# PCBschematic.net
KiCad netlist of a schematic drawn in EAGLE
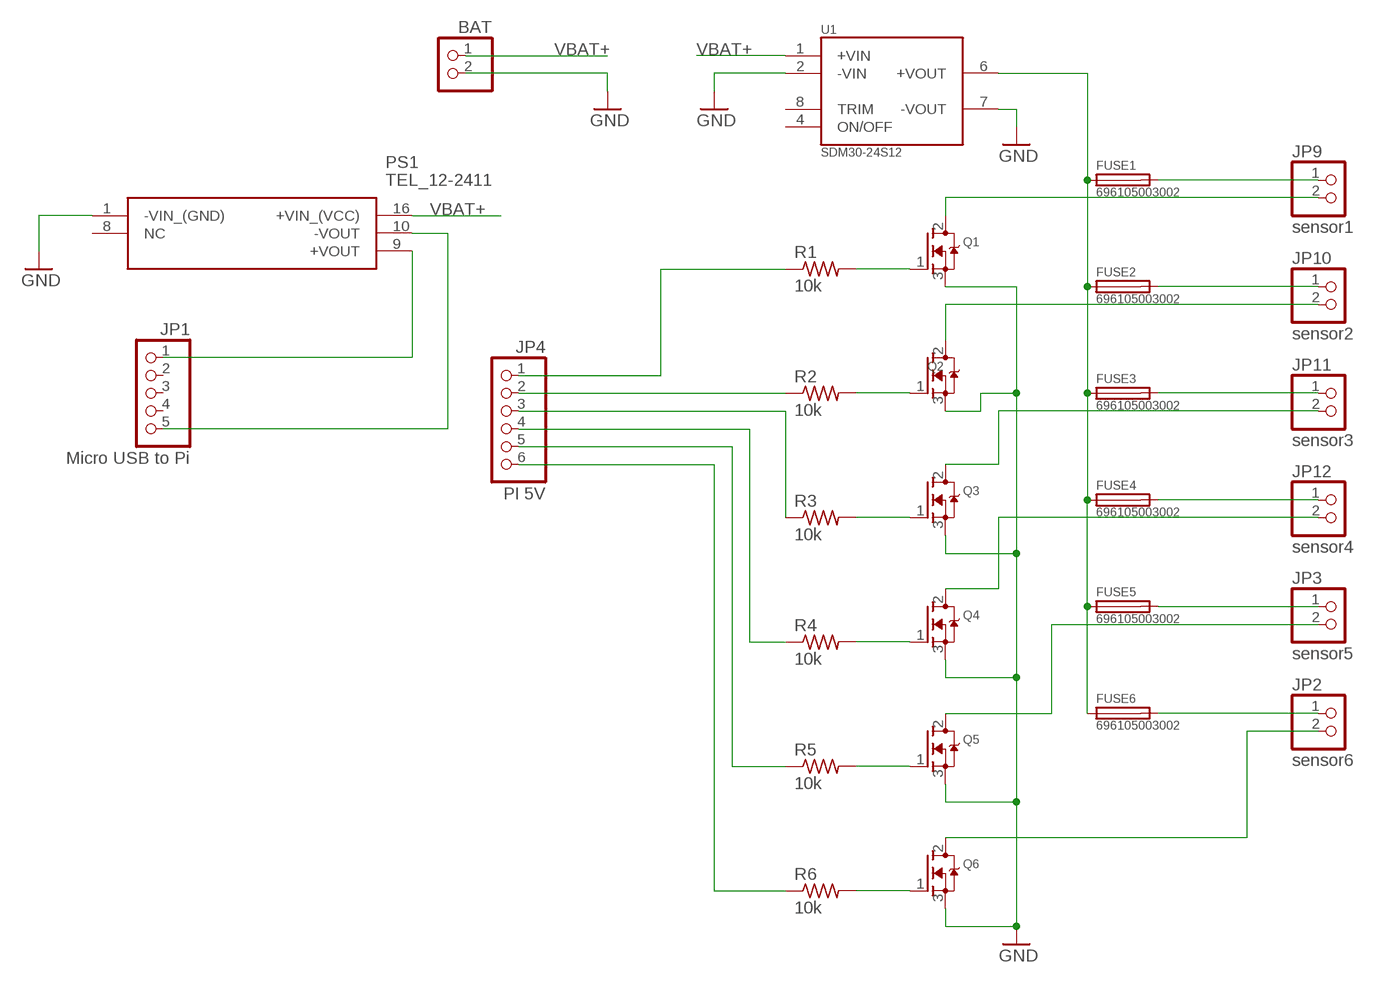
[diagram p0: schematic, sheet 1]

(export (version "E")
  (design (tool "Eeschema 10.0.6"))
  (components
    (comp (ref "BAT")
      (value "PINHD-1X2")
      (footprint "eagle-import:1X02")
      (libsource (lib "eagle-import") (part "PINHD-1X2"))
    )
    (comp (ref "FUSE1")
      (value "696105003002")
      (footprint "eagle-import:FUSE_696105003002")
      (fields (field (name "MF") "Wurth Electronics"))
      (libsource (lib "eagle-import") (part "696105003002"))
    )
    (comp (ref "FUSE2")
      (value "696105003002")
      (footprint "eagle-import:FUSE_696105003002")
      (fields (field (name "MF") "Wurth Electronics"))
      (libsource (lib "eagle-import") (part "696105003002"))
    )
    (comp (ref "FUSE3")
      (value "696105003002")
      (footprint "eagle-import:FUSE_696105003002")
      (fields (field (name "MF") "Wurth Electronics"))
      (libsource (lib "eagle-import") (part "696105003002"))
    )
    (comp (ref "FUSE4")
      (value "696105003002")
      (footprint "eagle-import:FUSE_696105003002")
      (fields (field (name "MF") "Wurth Electronics"))
      (libsource (lib "eagle-import") (part "696105003002"))
    )
    (comp (ref "FUSE5")
      (value "696105003002")
      (footprint "eagle-import:FUSE_696105003002")
      (fields (field (name "MF") "Wurth Electronics"))
      (libsource (lib "eagle-import") (part "696105003002"))
    )
    (comp (ref "FUSE6")
      (value "696105003002")
      (footprint "eagle-import:FUSE_696105003002")
      (fields (field (name "MF") "Wurth Electronics"))
      (libsource (lib "eagle-import") (part "696105003002"))
    )
    (comp (ref "JP1")
      (value "Micro USB to Pi")
      (footprint "eagle-import:1X05")
      (libsource (lib "eagle-import") (part "PINHD-1X5"))
    )
    (comp (ref "JP2")
      (value "sensor6")
      (footprint "eagle-import:1X02")
      (libsource (lib "eagle-import") (part "PINHD-1X2"))
    )
    (comp (ref "JP3")
      (value "sensor5")
      (footprint "eagle-import:1X02")
      (libsource (lib "eagle-import") (part "PINHD-1X2"))
    )
    (comp (ref "JP4")
      (value "PI 5V")
      (footprint "eagle-import:1X06")
      (libsource (lib "eagle-import") (part "PINHD-1X6"))
    )
    (comp (ref "JP9")
      (value "sensor1")
      (footprint "eagle-import:1X02")
      (libsource (lib "eagle-import") (part "PINHD-1X2"))
    )
    (comp (ref "JP10")
      (value "sensor2")
      (footprint "eagle-import:1X02")
      (libsource (lib "eagle-import") (part "PINHD-1X2"))
    )
    (comp (ref "JP11")
      (value "sensor3")
      (footprint "eagle-import:1X02")
      (libsource (lib "eagle-import") (part "PINHD-1X2"))
    )
    (comp (ref "JP12")
      (value "sensor4")
      (footprint "eagle-import:1X02")
      (libsource (lib "eagle-import") (part "PINHD-1X2"))
    )
    (comp (ref "PS1")
      (value "TEL_12-2411")
      (footprint "eagle-import:TEL122411")
      (fields
        (field (name "MANUFACTURER_PART_NUMBER") "TEL 12-2411")
        (field (name "MOUSER_PART_NUMBER") "495-TEL12-2411")
      )
      (libsource (lib "eagle-import") (part "TEL_12-2411"))
    )
    (comp (ref "Q1")
      (value "MOSFET-NGDS_TO220V")
      (footprint "eagle-import:TO220V")
      (libsource (lib "eagle-import") (part "MOSFET-NGDS_TO220V"))
    )
    (comp (ref "Q2")
      (value "MOSFET-NGDS_TO220V")
      (footprint "eagle-import:TO220V")
      (libsource (lib "eagle-import") (part "MOSFET-NGDS_TO220V"))
    )
    (comp (ref "Q3")
      (value "MOSFET-NGDS_TO220V")
      (footprint "eagle-import:TO220V")
      (libsource (lib "eagle-import") (part "MOSFET-NGDS_TO220V"))
    )
    (comp (ref "Q4")
      (value "MOSFET-NGDS_TO220V")
      (footprint "eagle-import:TO220V")
      (libsource (lib "eagle-import") (part "MOSFET-NGDS_TO220V"))
    )
    (comp (ref "Q5")
      (value "MOSFET-NGDS_TO220V")
      (footprint "eagle-import:TO220V")
      (libsource (lib "eagle-import") (part "MOSFET-NGDS_TO220V"))
    )
    (comp (ref "Q6")
      (value "MOSFET-NGDS_TO220V")
      (footprint "eagle-import:TO220V")
      (libsource (lib "eagle-import") (part "MOSFET-NGDS_TO220V"))
    )
    (comp (ref "R1")
      (value "10k")
      (footprint "eagle-import:M0805")
      (libsource (lib "eagle-import") (part "R-US_M0805"))
    )
    (comp (ref "R2")
      (value "10k")
      (footprint "eagle-import:M0805")
      (libsource (lib "eagle-import") (part "R-US_M0805"))
    )
    (comp (ref "R3")
      (value "10k")
      (footprint "eagle-import:M0805")
      (libsource (lib "eagle-import") (part "R-US_M0805"))
    )
    (comp (ref "R4")
      (value "10k")
      (footprint "eagle-import:M0805")
      (libsource (lib "eagle-import") (part "R-US_M0805"))
    )
    (comp (ref "R5")
      (value "10k")
      (footprint "eagle-import:M0805")
      (libsource (lib "eagle-import") (part "R-US_M0805"))
    )
    (comp (ref "R6")
      (value "10k")
      (footprint "eagle-import:M0805")
      (libsource (lib "eagle-import") (part "R-US_M0805"))
    )
    (comp (ref "U1")
      (value "SDM30-24S12")
      (footprint "eagle-import:CONV_SDM30-24S12")
      (fields (field (name "DIGI-KEY_PART_NUMBER") "1866-4449-ND") (field (name "MF") "MEAN WELL"))
      (libsource (lib "eagle-import") (part "SDM30-24S12"))
    )
  )
  (nets
    (net (code "1") (name "/VBAT+") (class "Default")
      (node (ref "BAT") (pin "1") (pinfunction "1_1") (pintype "passive"))
      (node (ref "PS1") (pin "16") (pinfunction "+VIN_(VCC)_16") (pintype "bidirectional"))
      (node (ref "U1") (pin "1") (pinfunction "+VIN_1") (pintype "input"))
    )
    (net (code "2") (name "GND") (class "Default")
      (node (ref "BAT") (pin "2") (pinfunction "2_2") (pintype "passive"))
      (node (ref "PS1") (pin "1") (pinfunction "-VIN_(GND)_1") (pintype "bidirectional"))
      (node (ref "Q1") (pin "3") (pinfunction "S_3") (pintype "bidirectional"))
      (node (ref "Q2") (pin "3") (pinfunction "S_3") (pintype "bidirectional"))
      (node (ref "Q3") (pin "3") (pinfunction "S_3") (pintype "bidirectional"))
      (node (ref "Q4") (pin "3") (pinfunction "S_3") (pintype "bidirectional"))
      (node (ref "Q5") (pin "3") (pinfunction "S_3") (pintype "bidirectional"))
      (node (ref "Q6") (pin "3") (pinfunction "S_3") (pintype "bidirectional"))
      (node (ref "U1") (pin "2") (pinfunction "-VIN_2") (pintype "input"))
      (node (ref "U1") (pin "7") (pinfunction "-VOUT_7") (pintype "output"))
    )
    (net (code "3") (name "Net-(FUSE1-Pad2)") (class "Default")
      (node (ref "FUSE1") (pin "2") (pinfunction "2_2") (pintype "passive"))
      (node (ref "JP9") (pin "1") (pinfunction "1_1") (pintype "passive"))
    )
    (net (code "4") (name "Net-(FUSE2-Pad2)") (class "Default")
      (node (ref "FUSE2") (pin "2") (pinfunction "2_2") (pintype "passive"))
      (node (ref "JP10") (pin "1") (pinfunction "1_1") (pintype "passive"))
    )
    (net (code "5") (name "Net-(FUSE3-Pad2)") (class "Default")
      (node (ref "FUSE3") (pin "2") (pinfunction "2_2") (pintype "passive"))
      (node (ref "JP11") (pin "1") (pinfunction "1_1") (pintype "passive"))
    )
    (net (code "6") (name "Net-(FUSE4-Pad2)") (class "Default")
      (node (ref "FUSE4") (pin "2") (pinfunction "2_2") (pintype "passive"))
      (node (ref "JP12") (pin "1") (pinfunction "1_1") (pintype "passive"))
    )
    (net (code "7") (name "Net-(FUSE5-Pad2)") (class "Default")
      (node (ref "FUSE5") (pin "2") (pinfunction "2_2") (pintype "passive"))
      (node (ref "JP3") (pin "1") (pinfunction "1_1") (pintype "passive"))
    )
    (net (code "8") (name "Net-(FUSE6-Pad2)") (class "Default")
      (node (ref "FUSE6") (pin "2") (pinfunction "2_2") (pintype "passive"))
      (node (ref "JP2") (pin "1") (pinfunction "1_1") (pintype "passive"))
    )
    (net (code "9") (name "Net-(JP4-Pad1)") (class "Default")
      (node (ref "JP4") (pin "1") (pinfunction "1_1") (pintype "passive"))
      (node (ref "R1") (pin "1") (pinfunction "1_1") (pintype "passive"))
    )
    (net (code "10") (name "Net-(JP4-Pad2)") (class "Default")
      (node (ref "JP4") (pin "2") (pinfunction "2_2") (pintype "passive"))
      (node (ref "R2") (pin "1") (pinfunction "1_1") (pintype "passive"))
    )
    (net (code "11") (name "Net-(JP4-Pad3)") (class "Default")
      (node (ref "JP4") (pin "3") (pinfunction "3_3") (pintype "passive"))
      (node (ref "R3") (pin "1") (pinfunction "1_1") (pintype "passive"))
    )
    (net (code "12") (name "Net-(JP4-Pad4)") (class "Default")
      (node (ref "JP4") (pin "4") (pinfunction "4_4") (pintype "passive"))
      (node (ref "R4") (pin "1") (pinfunction "1_1") (pintype "passive"))
    )
    (net (code "13") (name "Net-(JP4-Pad5)") (class "Default")
      (node (ref "JP4") (pin "5") (pinfunction "5_5") (pintype "passive"))
      (node (ref "R5") (pin "1") (pinfunction "1_1") (pintype "passive"))
    )
    (net (code "14") (name "Net-(JP4-Pad6)") (class "Default")
      (node (ref "JP4") (pin "6") (pinfunction "6_6") (pintype "passive"))
      (node (ref "R6") (pin "1") (pinfunction "1_1") (pintype "passive"))
    )
    (net (code "15") (name "Net-(PS1-+VOUT)") (class "Default")
      (node (ref "JP1") (pin "1") (pinfunction "1_1") (pintype "passive"))
      (node (ref "PS1") (pin "9") (pinfunction "+VOUT_9") (pintype "bidirectional"))
    )
    (net (code "16") (name "Net-(PS1--VOUT)") (class "Default")
      (node (ref "JP1") (pin "5") (pinfunction "5_5") (pintype "passive"))
      (node (ref "PS1") (pin "10") (pinfunction "-VOUT_10") (pintype "bidirectional"))
    )
    (net (code "17") (name "Net-(Q1-D)") (class "Default")
      (node (ref "JP9") (pin "2") (pinfunction "2_2") (pintype "passive"))
      (node (ref "Q1") (pin "2") (pinfunction "D_2") (pintype "bidirectional"))
    )
    (net (code "18") (name "Net-(Q1-G)") (class "Default")
      (node (ref "Q1") (pin "1") (pinfunction "G_1") (pintype "bidirectional"))
      (node (ref "R1") (pin "2") (pinfunction "2_2") (pintype "passive"))
    )
    (net (code "19") (name "Net-(Q2-D)") (class "Default")
      (node (ref "JP10") (pin "2") (pinfunction "2_2") (pintype "passive"))
      (node (ref "Q2") (pin "2") (pinfunction "D_2") (pintype "bidirectional"))
    )
    (net (code "20") (name "Net-(Q2-G)") (class "Default")
      (node (ref "Q2") (pin "1") (pinfunction "G_1") (pintype "bidirectional"))
      (node (ref "R2") (pin "2") (pinfunction "2_2") (pintype "passive"))
    )
    (net (code "21") (name "Net-(Q3-D)") (class "Default")
      (node (ref "JP11") (pin "2") (pinfunction "2_2") (pintype "passive"))
      (node (ref "Q3") (pin "2") (pinfunction "D_2") (pintype "bidirectional"))
    )
    (net (code "22") (name "Net-(Q3-G)") (class "Default")
      (node (ref "Q3") (pin "1") (pinfunction "G_1") (pintype "bidirectional"))
      (node (ref "R3") (pin "2") (pinfunction "2_2") (pintype "passive"))
    )
    (net (code "23") (name "Net-(Q4-D)") (class "Default")
      (node (ref "JP12") (pin "2") (pinfunction "2_2") (pintype "passive"))
      (node (ref "Q4") (pin "2") (pinfunction "D_2") (pintype "bidirectional"))
    )
    (net (code "24") (name "Net-(Q4-G)") (class "Default")
      (node (ref "Q4") (pin "1") (pinfunction "G_1") (pintype "bidirectional"))
      (node (ref "R4") (pin "2") (pinfunction "2_2") (pintype "passive"))
    )
    (net (code "25") (name "Net-(Q5-D)") (class "Default")
      (node (ref "JP3") (pin "2") (pinfunction "2_2") (pintype "passive"))
      (node (ref "Q5") (pin "2") (pinfunction "D_2") (pintype "bidirectional"))
    )
    (net (code "26") (name "Net-(Q5-G)") (class "Default")
      (node (ref "Q5") (pin "1") (pinfunction "G_1") (pintype "bidirectional"))
      (node (ref "R5") (pin "2") (pinfunction "2_2") (pintype "passive"))
    )
    (net (code "27") (name "Net-(Q6-D)") (class "Default")
      (node (ref "JP2") (pin "2") (pinfunction "2_2") (pintype "passive"))
      (node (ref "Q6") (pin "2") (pinfunction "D_2") (pintype "bidirectional"))
    )
    (net (code "28") (name "Net-(Q6-G)") (class "Default")
      (node (ref "Q6") (pin "1") (pinfunction "G_1") (pintype "bidirectional"))
      (node (ref "R6") (pin "2") (pinfunction "2_2") (pintype "passive"))
    )
    (net (code "29") (name "Net-(U1-+VOUT)") (class "Default")
      (node (ref "FUSE1") (pin "1") (pinfunction "1_1") (pintype "passive"))
      (node (ref "FUSE2") (pin "1") (pinfunction "1_1") (pintype "passive"))
      (node (ref "FUSE3") (pin "1") (pinfunction "1_1") (pintype "passive"))
      (node (ref "FUSE4") (pin "1") (pinfunction "1_1") (pintype "passive"))
      (node (ref "FUSE5") (pin "1") (pinfunction "1_1") (pintype "passive"))
      (node (ref "FUSE6") (pin "1") (pinfunction "1_1") (pintype "passive"))
      (node (ref "U1") (pin "6") (pinfunction "+VOUT_6") (pintype "output"))
    )
    (net (code "30") (name "unconnected-(JP1-Pad2)") (class "Default")
      (node (ref "JP1") (pin "2") (pinfunction "2_2") (pintype "passive"))
    )
    (net (code "31") (name "unconnected-(JP1-Pad3)") (class "Default")
      (node (ref "JP1") (pin "3") (pinfunction "3_3") (pintype "passive"))
    )
    (net (code "32") (name "unconnected-(JP1-Pad4)") (class "Default")
      (node (ref "JP1") (pin "4") (pinfunction "4_4") (pintype "passive"))
    )
    (net (code "33") (name "unconnected-(PS1-NC-Pad8)") (class "Default")
      (node (ref "PS1") (pin "8") (pinfunction "NC_8") (pintype "no_connect"))
    )
    (net (code "34") (name "unconnected-(U1-ON{slash}OFF-Pad4)") (class "Default")
      (node (ref "U1") (pin "4") (pinfunction "ON/OFF_4") (pintype "input"))
    )
    (net (code "35") (name "unconnected-(U1-TRIM-Pad8)") (class "Default")
      (node (ref "U1") (pin "8") (pinfunction "TRIM_8") (pintype "input"))
    )
  )
)
